# Sheet1.net
KiCad netlist of a schematic drawn in Altium Designer
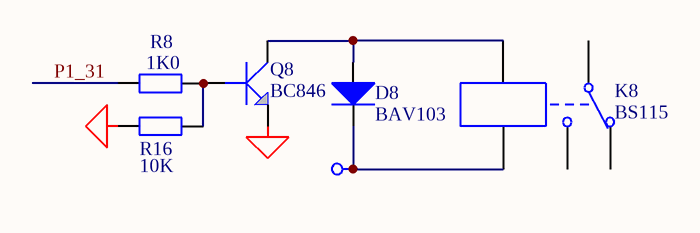
[diagram p0: Sheet1.SchDoc]

(export (version "E")
  (design (tool "Eeschema 10.0.6"))
  (components
    (comp (ref "D8")
      (value "BAV103")
      (footprint "_1206d")
      (description "Diode")
      (fields (field (name "MANUFACTURER") "Generic Components") (field (name "PUBLISHER") "Altium Limited"))
      (libsource (lib "PAL") (part "Diode"))
    )
    (comp (ref "K8")
      (value "BS115")
      (footprint "bs115")
      (description "Single-Pole Dual-Throw Relay")
      (fields (field (name "MANUFACTURER") "Generic Components") (field (name "PUBLISHER") "Altium Limited"))
      (libsource (lib "PAL") (part "BS115"))
    )
    (comp (ref "Q8")
      (value "BC846")
      (footprint "SO-G3")
      (description "Bipolar transistor")
      (libsource (lib "MAIN") (part "GT122"))
    )
    (comp (ref "R8")
      (value "1K0")
      (footprint "_1206")
      (description "Resistor")
      (fields (field (name "MANUFACTURER") "Generic Components") (field (name "PUBLISHER") "Altium Limited"))
      (libsource (lib "Miscellaneous Devices") (part "Res2"))
    )
    (comp (ref "R16")
      (value "10K")
      (footprint "_1206")
      (description "Resistor")
      (fields (field (name "MANUFACTURER") "Generic Components") (field (name "PUBLISHER") "Altium Limited"))
      (libsource (lib "Miscellaneous Devices") (part "Res2"))
    )
  )
  (nets
    (net (code "1") (name "+5v") (class "Default")
      (node (ref "D8") (pin "2") (pinfunction "K_2") (pintype "passive"))
      (node (ref "K8") (pin "5") (pinfunction "5_5") (pintype "passive"))
    )
    (net (code "2") (name "/P1_31") (class "Default")
      (node (ref "R8") (pin "1") (pinfunction "1_1") (pintype "passive"))
    )
    (net (code "3") (name "GND") (class "Default")
      (node (ref "Q8") (pin "2") (pinfunction "E_2") (pintype "passive"))
      (node (ref "R16") (pin "1") (pinfunction "1_1") (pintype "passive"))
    )
    (net (code "4") (name "Net-(D8-A)") (class "Default")
      (node (ref "D8") (pin "1") (pinfunction "A_1") (pintype "passive"))
      (node (ref "K8") (pin "4") (pinfunction "4_4") (pintype "passive"))
      (node (ref "Q8") (pin "3") (pinfunction "C_3") (pintype "passive"))
    )
    (net (code "5") (name "Net-(Q8-B)") (class "Default")
      (node (ref "Q8") (pin "1") (pinfunction "B_1") (pintype "passive"))
      (node (ref "R16") (pin "2") (pinfunction "2_2") (pintype "passive"))
      (node (ref "R8") (pin "2") (pinfunction "2_2") (pintype "passive"))
    )
    (net (code "6") (name "unconnected-(K8-Pad1)") (class "Default")
      (node (ref "K8") (pin "1") (pinfunction "1_1") (pintype "passive"))
    )
    (net (code "7") (name "unconnected-(K8-Pad2)") (class "Default")
      (node (ref "K8") (pin "2") (pinfunction "2_2") (pintype "passive"))
    )
    (net (code "8") (name "unconnected-(K8-Pad3)") (class "Default")
      (node (ref "K8") (pin "3") (pinfunction "3_3") (pintype "passive"))
    )
  )
)
